# Enconder_Part2.net
KiCad netlist of a schematic drawn in Altium Designer
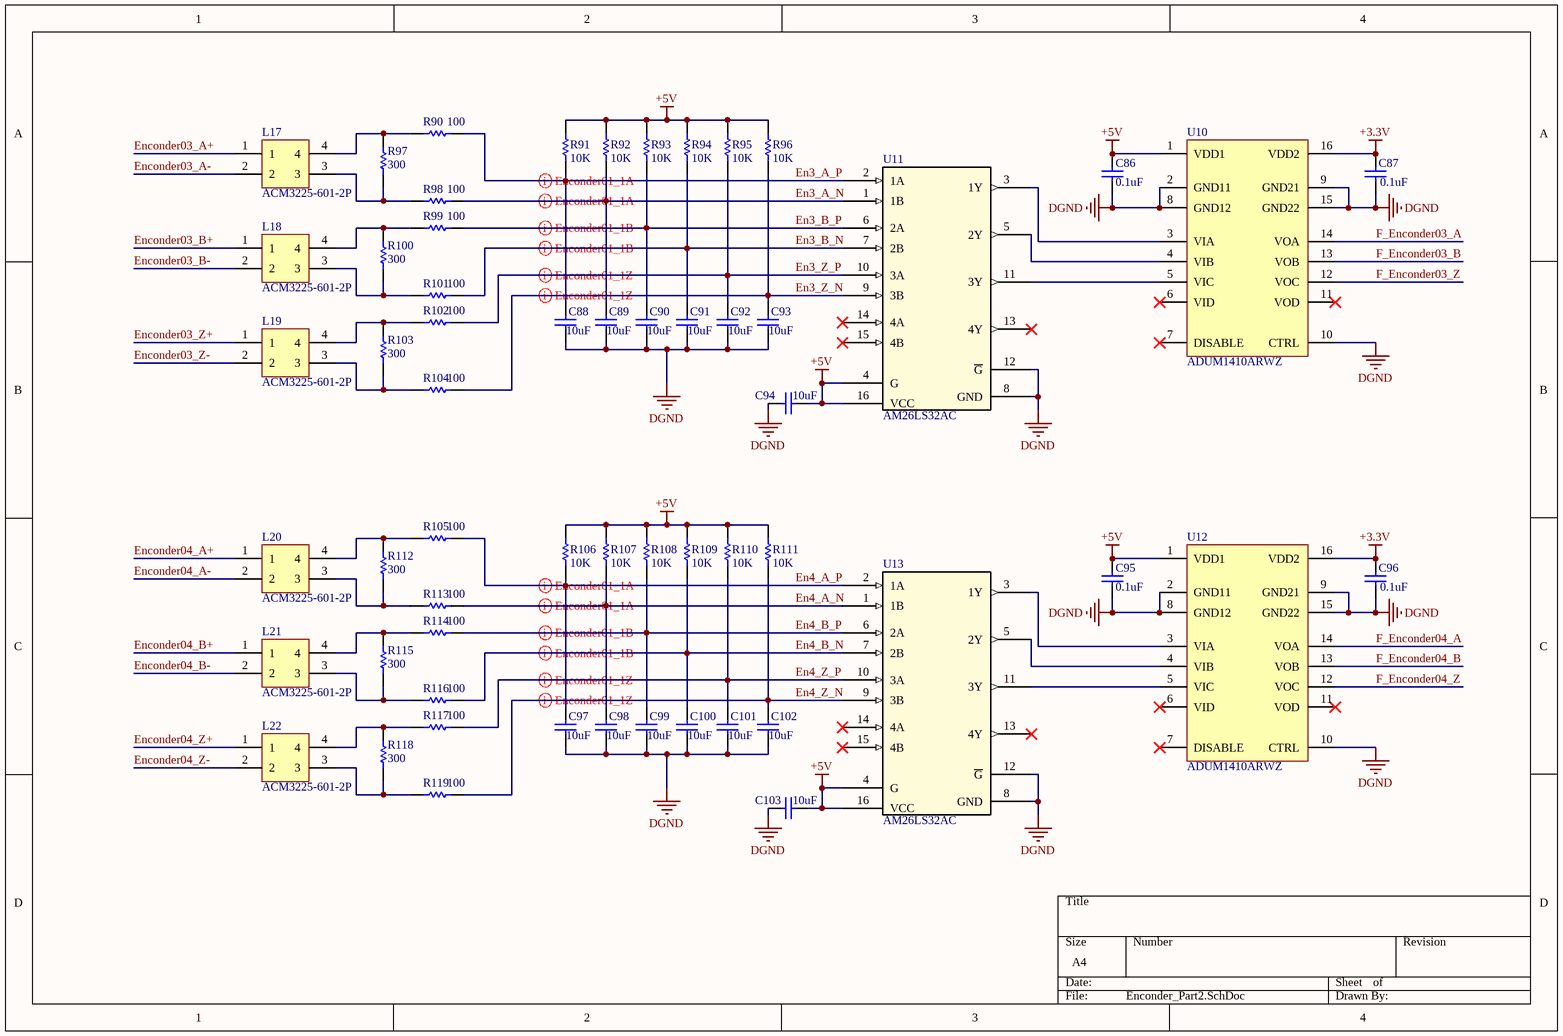
[diagram p0: Enconder_Part2.SchDoc]

(export (version "E")
  (design (tool "Eeschema 10.0.6"))
  (components
    (comp (ref "C86")
      (value "0.1uF")
      (footprint "1608[0603]")
      (description "Capacitor")
      (fields (field (name "Comment") "Cap") (field (name "PUBLISHER") "Altium Limited"))
      (libsource (lib "Miscellaneous Devices") (part "Cap"))
    )
    (comp (ref "C87")
      (value "0.1uF")
      (footprint "1608[0603]")
      (description "Capacitor")
      (fields (field (name "Comment") "Cap") (field (name "PUBLISHER") "Altium Limited"))
      (libsource (lib "Miscellaneous Devices") (part "Cap"))
    )
    (comp (ref "C88")
      (value "10uF")
      (footprint "1608[0603]")
      (description "Capacitor")
      (fields (field (name "Comment") "Cap") (field (name "PUBLISHER") "Altium Limited"))
      (libsource (lib "Miscellaneous Devices") (part "Cap"))
    )
    (comp (ref "C89")
      (value "10uF")
      (footprint "1608[0603]")
      (description "Capacitor")
      (fields (field (name "Comment") "Cap") (field (name "PUBLISHER") "Altium Limited"))
      (libsource (lib "Miscellaneous Devices") (part "Cap"))
    )
    (comp (ref "C90")
      (value "10uF")
      (footprint "1608[0603]")
      (description "Capacitor")
      (fields (field (name "Comment") "Cap") (field (name "PUBLISHER") "Altium Limited"))
      (libsource (lib "Miscellaneous Devices") (part "Cap"))
    )
    (comp (ref "C91")
      (value "10uF")
      (footprint "1608[0603]")
      (description "Capacitor")
      (fields (field (name "Comment") "Cap") (field (name "PUBLISHER") "Altium Limited"))
      (libsource (lib "Miscellaneous Devices") (part "Cap"))
    )
    (comp (ref "C92")
      (value "10uF")
      (footprint "1608[0603]")
      (description "Capacitor")
      (fields (field (name "Comment") "Cap") (field (name "PUBLISHER") "Altium Limited"))
      (libsource (lib "Miscellaneous Devices") (part "Cap"))
    )
    (comp (ref "C93")
      (value "10uF")
      (footprint "1608[0603]")
      (description "Capacitor")
      (fields (field (name "Comment") "Cap") (field (name "PUBLISHER") "Altium Limited"))
      (libsource (lib "Miscellaneous Devices") (part "Cap"))
    )
    (comp (ref "C94")
      (value "10uF")
      (footprint "1608[0603]")
      (description "Capacitor")
      (fields (field (name "Comment") "Cap") (field (name "PUBLISHER") "Altium Limited"))
      (libsource (lib "Miscellaneous Devices") (part "Cap"))
    )
    (comp (ref "C95")
      (value "0.1uF")
      (footprint "1608[0603]")
      (description "Capacitor")
      (fields (field (name "Comment") "Cap") (field (name "PUBLISHER") "Altium Limited"))
      (libsource (lib "Miscellaneous Devices") (part "Cap"))
    )
    (comp (ref "C96")
      (value "0.1uF")
      (footprint "1608[0603]")
      (description "Capacitor")
      (fields (field (name "Comment") "Cap") (field (name "PUBLISHER") "Altium Limited"))
      (libsource (lib "Miscellaneous Devices") (part "Cap"))
    )
    (comp (ref "C97")
      (value "10uF")
      (footprint "1608[0603]")
      (description "Capacitor")
      (fields (field (name "Comment") "Cap") (field (name "PUBLISHER") "Altium Limited"))
      (libsource (lib "Miscellaneous Devices") (part "Cap"))
    )
    (comp (ref "C98")
      (value "10uF")
      (footprint "1608[0603]")
      (description "Capacitor")
      (fields (field (name "Comment") "Cap") (field (name "PUBLISHER") "Altium Limited"))
      (libsource (lib "Miscellaneous Devices") (part "Cap"))
    )
    (comp (ref "C99")
      (value "10uF")
      (footprint "1608[0603]")
      (description "Capacitor")
      (fields (field (name "Comment") "Cap") (field (name "PUBLISHER") "Altium Limited"))
      (libsource (lib "Miscellaneous Devices") (part "Cap"))
    )
    (comp (ref "C100")
      (value "10uF")
      (footprint "1608[0603]")
      (description "Capacitor")
      (fields (field (name "Comment") "Cap") (field (name "PUBLISHER") "Altium Limited"))
      (libsource (lib "Miscellaneous Devices") (part "Cap"))
    )
    (comp (ref "C101")
      (value "10uF")
      (footprint "1608[0603]")
      (description "Capacitor")
      (fields (field (name "Comment") "Cap") (field (name "PUBLISHER") "Altium Limited"))
      (libsource (lib "Miscellaneous Devices") (part "Cap"))
    )
    (comp (ref "C102")
      (value "10uF")
      (footprint "1608[0603]")
      (description "Capacitor")
      (fields (field (name "Comment") "Cap") (field (name "PUBLISHER") "Altium Limited"))
      (libsource (lib "Miscellaneous Devices") (part "Cap"))
    )
    (comp (ref "C103")
      (value "10uF")
      (footprint "1608[0603]")
      (description "Capacitor")
      (fields (field (name "Comment") "Cap") (field (name "PUBLISHER") "Altium Limited"))
      (libsource (lib "Miscellaneous Devices") (part "Cap"))
    )
    (comp (ref "L17")
      (value "ACM3225-601-2P")
      (footprint "ACM3225-601-2P")
      (libsource (lib "DSP_FPGA_Lib") (part "ACM3225-601-2P"))
    )
    (comp (ref "L18")
      (value "ACM3225-601-2P")
      (footprint "ACM3225-601-2P")
      (libsource (lib "DSP_FPGA_Lib") (part "ACM3225-601-2P"))
    )
    (comp (ref "L19")
      (value "ACM3225-601-2P")
      (footprint "ACM3225-601-2P")
      (libsource (lib "DSP_FPGA_Lib") (part "ACM3225-601-2P"))
    )
    (comp (ref "L20")
      (value "ACM3225-601-2P")
      (footprint "ACM3225-601-2P")
      (libsource (lib "DSP_FPGA_Lib") (part "ACM3225-601-2P"))
    )
    (comp (ref "L21")
      (value "ACM3225-601-2P")
      (footprint "ACM3225-601-2P")
      (libsource (lib "DSP_FPGA_Lib") (part "ACM3225-601-2P"))
    )
    (comp (ref "L22")
      (value "ACM3225-601-2P")
      (footprint "ACM3225-601-2P")
      (libsource (lib "DSP_FPGA_Lib") (part "ACM3225-601-2P"))
    )
    (comp (ref "R90")
      (value "100")
      (footprint "1608[0603]")
      (description "Resistor")
      (fields (field (name "Comment") "Res1") (field (name "PUBLISHER") "Altium Limited"))
      (libsource (lib "Miscellaneous Devices") (part "Res1"))
    )
    (comp (ref "R91")
      (value "10K")
      (footprint "1608[0603]")
      (description "Resistor")
      (fields (field (name "Comment") "Res1") (field (name "PUBLISHER") "Altium Limited"))
      (libsource (lib "Miscellaneous Devices") (part "Res1"))
    )
    (comp (ref "R92")
      (value "10K")
      (footprint "1608[0603]")
      (description "Resistor")
      (fields (field (name "Comment") "Res1") (field (name "PUBLISHER") "Altium Limited"))
      (libsource (lib "Miscellaneous Devices") (part "Res1"))
    )
    (comp (ref "R93")
      (value "10K")
      (footprint "1608[0603]")
      (description "Resistor")
      (fields (field (name "Comment") "Res1") (field (name "PUBLISHER") "Altium Limited"))
      (libsource (lib "Miscellaneous Devices") (part "Res1"))
    )
    (comp (ref "R94")
      (value "10K")
      (footprint "1608[0603]")
      (description "Resistor")
      (fields (field (name "Comment") "Res1") (field (name "PUBLISHER") "Altium Limited"))
      (libsource (lib "Miscellaneous Devices") (part "Res1"))
    )
    (comp (ref "R95")
      (value "10K")
      (footprint "1608[0603]")
      (description "Resistor")
      (fields (field (name "Comment") "Res1") (field (name "PUBLISHER") "Altium Limited"))
      (libsource (lib "Miscellaneous Devices") (part "Res1"))
    )
    (comp (ref "R96")
      (value "10K")
      (footprint "1608[0603]")
      (description "Resistor")
      (fields (field (name "Comment") "Res1") (field (name "PUBLISHER") "Altium Limited"))
      (libsource (lib "Miscellaneous Devices") (part "Res1"))
    )
    (comp (ref "R97")
      (value "300")
      (footprint "1608[0603]")
      (description "Resistor")
      (fields (field (name "Comment") "Res1") (field (name "PUBLISHER") "Altium Limited"))
      (libsource (lib "Miscellaneous Devices") (part "Res1"))
    )
    (comp (ref "R98")
      (value "100")
      (footprint "1608[0603]")
      (description "Resistor")
      (fields (field (name "Comment") "Res1") (field (name "PUBLISHER") "Altium Limited"))
      (libsource (lib "Miscellaneous Devices") (part "Res1"))
    )
    (comp (ref "R99")
      (value "100")
      (footprint "1608[0603]")
      (description "Resistor")
      (fields (field (name "Comment") "Res1") (field (name "PUBLISHER") "Altium Limited"))
      (libsource (lib "Miscellaneous Devices") (part "Res1"))
    )
    (comp (ref "R100")
      (value "300")
      (footprint "1608[0603]")
      (description "Resistor")
      (fields (field (name "Comment") "Res1") (field (name "PUBLISHER") "Altium Limited"))
      (libsource (lib "Miscellaneous Devices") (part "Res1"))
    )
    (comp (ref "R101")
      (value "100")
      (footprint "1608[0603]")
      (description "Resistor")
      (fields (field (name "Comment") "Res1") (field (name "PUBLISHER") "Altium Limited"))
      (libsource (lib "Miscellaneous Devices") (part "Res1"))
    )
    (comp (ref "R102")
      (value "100")
      (footprint "1608[0603]")
      (description "Resistor")
      (fields (field (name "Comment") "Res1") (field (name "PUBLISHER") "Altium Limited"))
      (libsource (lib "Miscellaneous Devices") (part "Res1"))
    )
    (comp (ref "R103")
      (value "300")
      (footprint "1608[0603]")
      (description "Resistor")
      (fields (field (name "Comment") "Res1") (field (name "PUBLISHER") "Altium Limited"))
      (libsource (lib "Miscellaneous Devices") (part "Res1"))
    )
    (comp (ref "R104")
      (value "100")
      (footprint "1608[0603]")
      (description "Resistor")
      (fields (field (name "Comment") "Res1") (field (name "PUBLISHER") "Altium Limited"))
      (libsource (lib "Miscellaneous Devices") (part "Res1"))
    )
    (comp (ref "R105")
      (value "100")
      (footprint "1608[0603]")
      (description "Resistor")
      (fields (field (name "Comment") "Res1") (field (name "PUBLISHER") "Altium Limited"))
      (libsource (lib "Miscellaneous Devices") (part "Res1"))
    )
    (comp (ref "R106")
      (value "10K")
      (footprint "1608[0603]")
      (description "Resistor")
      (fields (field (name "Comment") "Res1") (field (name "PUBLISHER") "Altium Limited"))
      (libsource (lib "Miscellaneous Devices") (part "Res1"))
    )
    (comp (ref "R107")
      (value "10K")
      (footprint "1608[0603]")
      (description "Resistor")
      (fields (field (name "Comment") "Res1") (field (name "PUBLISHER") "Altium Limited"))
      (libsource (lib "Miscellaneous Devices") (part "Res1"))
    )
    (comp (ref "R108")
      (value "10K")
      (footprint "1608[0603]")
      (description "Resistor")
      (fields (field (name "Comment") "Res1") (field (name "PUBLISHER") "Altium Limited"))
      (libsource (lib "Miscellaneous Devices") (part "Res1"))
    )
    (comp (ref "R109")
      (value "10K")
      (footprint "1608[0603]")
      (description "Resistor")
      (fields (field (name "Comment") "Res1") (field (name "PUBLISHER") "Altium Limited"))
      (libsource (lib "Miscellaneous Devices") (part "Res1"))
    )
    (comp (ref "R110")
      (value "10K")
      (footprint "1608[0603]")
      (description "Resistor")
      (fields (field (name "Comment") "Res1") (field (name "PUBLISHER") "Altium Limited"))
      (libsource (lib "Miscellaneous Devices") (part "Res1"))
    )
    (comp (ref "R111")
      (value "10K")
      (footprint "1608[0603]")
      (description "Resistor")
      (fields (field (name "Comment") "Res1") (field (name "PUBLISHER") "Altium Limited"))
      (libsource (lib "Miscellaneous Devices") (part "Res1"))
    )
    (comp (ref "R112")
      (value "300")
      (footprint "1608[0603]")
      (description "Resistor")
      (fields (field (name "Comment") "Res1") (field (name "PUBLISHER") "Altium Limited"))
      (libsource (lib "Miscellaneous Devices") (part "Res1"))
    )
    (comp (ref "R113")
      (value "100")
      (footprint "1608[0603]")
      (description "Resistor")
      (fields (field (name "Comment") "Res1") (field (name "PUBLISHER") "Altium Limited"))
      (libsource (lib "Miscellaneous Devices") (part "Res1"))
    )
    (comp (ref "R114")
      (value "100")
      (footprint "1608[0603]")
      (description "Resistor")
      (fields (field (name "Comment") "Res1") (field (name "PUBLISHER") "Altium Limited"))
      (libsource (lib "Miscellaneous Devices") (part "Res1"))
    )
    (comp (ref "R115")
      (value "300")
      (footprint "1608[0603]")
      (description "Resistor")
      (fields (field (name "Comment") "Res1") (field (name "PUBLISHER") "Altium Limited"))
      (libsource (lib "Miscellaneous Devices") (part "Res1"))
    )
    (comp (ref "R116")
      (value "100")
      (footprint "1608[0603]")
      (description "Resistor")
      (fields (field (name "Comment") "Res1") (field (name "PUBLISHER") "Altium Limited"))
      (libsource (lib "Miscellaneous Devices") (part "Res1"))
    )
    (comp (ref "R117")
      (value "100")
      (footprint "1608[0603]")
      (description "Resistor")
      (fields (field (name "Comment") "Res1") (field (name "PUBLISHER") "Altium Limited"))
      (libsource (lib "Miscellaneous Devices") (part "Res1"))
    )
    (comp (ref "R118")
      (value "300")
      (footprint "1608[0603]")
      (description "Resistor")
      (fields (field (name "Comment") "Res1") (field (name "PUBLISHER") "Altium Limited"))
      (libsource (lib "Miscellaneous Devices") (part "Res1"))
    )
    (comp (ref "R119")
      (value "100")
      (footprint "1608[0603]")
      (description "Resistor")
      (fields (field (name "Comment") "Res1") (field (name "PUBLISHER") "Altium Limited"))
      (libsource (lib "Miscellaneous Devices") (part "Res1"))
    )
    (comp (ref "U10")
      (value "ADUM1410ARWZ")
      (footprint "ADUM1410ARWZ_SOIC")
      (libsource (lib "DSP_FPGA_Lib") (part "ADUM1410ARWZ"))
    )
    (comp (ref "U11")
      (value "AM26LS32AC")
      (footprint "AM26LS32AC_SOP")
      (libsource (lib "DSP_FPGA_Lib") (part "AM26LS32AC"))
    )
    (comp (ref "U12")
      (value "ADUM1410ARWZ")
      (footprint "ADUM1410ARWZ_SOIC")
      (libsource (lib "DSP_FPGA_Lib") (part "ADUM1410ARWZ"))
    )
    (comp (ref "U13")
      (value "AM26LS32AC")
      (footprint "AM26LS32AC_SOP")
      (libsource (lib "DSP_FPGA_Lib") (part "AM26LS32AC"))
    )
  )
  (nets
    (net (code "1") (name "+3.3V") (class "Default")
      (node (ref "C87") (pin "2") (pinfunction "2_2") (pintype "passive"))
      (node (ref "C96") (pin "2") (pinfunction "2_2") (pintype "passive"))
      (node (ref "U10") (pin "16") (pinfunction "VDD2_16") (pintype "passive"))
      (node (ref "U12") (pin "16") (pinfunction "VDD2_16") (pintype "passive"))
    )
    (net (code "2") (name "+5V") (class "Default")
      (node (ref "C103") (pin "1") (pinfunction "1_1") (pintype "passive"))
      (node (ref "C86") (pin "2") (pinfunction "2_2") (pintype "passive"))
      (node (ref "C94") (pin "1") (pinfunction "1_1") (pintype "passive"))
      (node (ref "C95") (pin "2") (pinfunction "2_2") (pintype "passive"))
      (node (ref "R106") (pin "2") (pinfunction "2_2") (pintype "passive"))
      (node (ref "R107") (pin "2") (pinfunction "2_2") (pintype "passive"))
      (node (ref "R108") (pin "2") (pinfunction "2_2") (pintype "passive"))
      (node (ref "R109") (pin "2") (pinfunction "2_2") (pintype "passive"))
      (node (ref "R110") (pin "2") (pinfunction "2_2") (pintype "passive"))
      (node (ref "R111") (pin "2") (pinfunction "2_2") (pintype "passive"))
      (node (ref "R91") (pin "2") (pinfunction "2_2") (pintype "passive"))
      (node (ref "R92") (pin "2") (pinfunction "2_2") (pintype "passive"))
      (node (ref "R93") (pin "2") (pinfunction "2_2") (pintype "passive"))
      (node (ref "R94") (pin "2") (pinfunction "2_2") (pintype "passive"))
      (node (ref "R95") (pin "2") (pinfunction "2_2") (pintype "passive"))
      (node (ref "R96") (pin "2") (pinfunction "2_2") (pintype "passive"))
      (node (ref "U10") (pin "1") (pinfunction "VDD1_1") (pintype "passive"))
      (node (ref "U11") (pin "16") (pinfunction "VCC_16") (pintype "power_in"))
      (node (ref "U11") (pin "4") (pinfunction "G_4") (pintype "passive"))
      (node (ref "U12") (pin "1") (pinfunction "VDD1_1") (pintype "passive"))
      (node (ref "U13") (pin "16") (pinfunction "VCC_16") (pintype "power_in"))
      (node (ref "U13") (pin "4") (pinfunction "G_4") (pintype "passive"))
    )
    (net (code "3") (name "/En3_A_N") (class "Default")
      (node (ref "C89") (pin "2") (pinfunction "2_2") (pintype "passive"))
      (node (ref "R92") (pin "1") (pinfunction "1_1") (pintype "passive"))
      (node (ref "R98") (pin "2") (pinfunction "2_2") (pintype "passive"))
      (node (ref "U11") (pin "1") (pinfunction "1B_1") (pintype "input"))
    )
    (net (code "4") (name "/En3_A_P") (class "Default")
      (node (ref "C88") (pin "2") (pinfunction "2_2") (pintype "passive"))
      (node (ref "R90") (pin "2") (pinfunction "2_2") (pintype "passive"))
      (node (ref "R91") (pin "1") (pinfunction "1_1") (pintype "passive"))
      (node (ref "U11") (pin "2") (pinfunction "1A_2") (pintype "input"))
    )
    (net (code "5") (name "/En3_B_N") (class "Default")
      (node (ref "C91") (pin "2") (pinfunction "2_2") (pintype "passive"))
      (node (ref "R101") (pin "2") (pinfunction "2_2") (pintype "passive"))
      (node (ref "R94") (pin "1") (pinfunction "1_1") (pintype "passive"))
      (node (ref "U11") (pin "7") (pinfunction "2B_7") (pintype "input"))
    )
    (net (code "6") (name "/En3_B_P") (class "Default")
      (node (ref "C90") (pin "2") (pinfunction "2_2") (pintype "passive"))
      (node (ref "R93") (pin "1") (pinfunction "1_1") (pintype "passive"))
      (node (ref "R99") (pin "2") (pinfunction "2_2") (pintype "passive"))
      (node (ref "U11") (pin "6") (pinfunction "2A_6") (pintype "input"))
    )
    (net (code "7") (name "/En3_Z_N") (class "Default")
      (node (ref "C93") (pin "2") (pinfunction "2_2") (pintype "passive"))
      (node (ref "R104") (pin "2") (pinfunction "2_2") (pintype "passive"))
      (node (ref "R96") (pin "1") (pinfunction "1_1") (pintype "passive"))
      (node (ref "U11") (pin "9") (pinfunction "3B_9") (pintype "input"))
    )
    (net (code "8") (name "/En3_Z_P") (class "Default")
      (node (ref "C92") (pin "2") (pinfunction "2_2") (pintype "passive"))
      (node (ref "R102") (pin "2") (pinfunction "2_2") (pintype "passive"))
      (node (ref "R95") (pin "1") (pinfunction "1_1") (pintype "passive"))
      (node (ref "U11") (pin "10") (pinfunction "3A_10") (pintype "input"))
    )
    (net (code "9") (name "/En4_A_N") (class "Default")
      (node (ref "C98") (pin "2") (pinfunction "2_2") (pintype "passive"))
      (node (ref "R107") (pin "1") (pinfunction "1_1") (pintype "passive"))
      (node (ref "R113") (pin "2") (pinfunction "2_2") (pintype "passive"))
      (node (ref "U13") (pin "1") (pinfunction "1B_1") (pintype "input"))
    )
    (net (code "10") (name "/En4_A_P") (class "Default")
      (node (ref "C97") (pin "2") (pinfunction "2_2") (pintype "passive"))
      (node (ref "R105") (pin "2") (pinfunction "2_2") (pintype "passive"))
      (node (ref "R106") (pin "1") (pinfunction "1_1") (pintype "passive"))
      (node (ref "U13") (pin "2") (pinfunction "1A_2") (pintype "input"))
    )
    (net (code "11") (name "/En4_B_N") (class "Default")
      (node (ref "C100") (pin "2") (pinfunction "2_2") (pintype "passive"))
      (node (ref "R109") (pin "1") (pinfunction "1_1") (pintype "passive"))
      (node (ref "R116") (pin "2") (pinfunction "2_2") (pintype "passive"))
      (node (ref "U13") (pin "7") (pinfunction "2B_7") (pintype "input"))
    )
    (net (code "12") (name "/En4_B_P") (class "Default")
      (node (ref "C99") (pin "2") (pinfunction "2_2") (pintype "passive"))
      (node (ref "R108") (pin "1") (pinfunction "1_1") (pintype "passive"))
      (node (ref "R114") (pin "2") (pinfunction "2_2") (pintype "passive"))
      (node (ref "U13") (pin "6") (pinfunction "2A_6") (pintype "input"))
    )
    (net (code "13") (name "/En4_Z_N") (class "Default")
      (node (ref "C102") (pin "2") (pinfunction "2_2") (pintype "passive"))
      (node (ref "R111") (pin "1") (pinfunction "1_1") (pintype "passive"))
      (node (ref "R119") (pin "2") (pinfunction "2_2") (pintype "passive"))
      (node (ref "U13") (pin "9") (pinfunction "3B_9") (pintype "input"))
    )
    (net (code "14") (name "/En4_Z_P") (class "Default")
      (node (ref "C101") (pin "2") (pinfunction "2_2") (pintype "passive"))
      (node (ref "R110") (pin "1") (pinfunction "1_1") (pintype "passive"))
      (node (ref "R117") (pin "2") (pinfunction "2_2") (pintype "passive"))
      (node (ref "U13") (pin "10") (pinfunction "3A_10") (pintype "input"))
    )
    (net (code "15") (name "/Enconder03_A+") (class "Default")
      (node (ref "L17") (pin "1") (pinfunction "1_1") (pintype "passive"))
    )
    (net (code "16") (name "/Enconder03_A-") (class "Default")
      (node (ref "L17") (pin "2") (pinfunction "2_2") (pintype "passive"))
    )
    (net (code "17") (name "/Enconder03_B+") (class "Default")
      (node (ref "L18") (pin "1") (pinfunction "1_1") (pintype "passive"))
    )
    (net (code "18") (name "/Enconder03_B-") (class "Default")
      (node (ref "L18") (pin "2") (pinfunction "2_2") (pintype "passive"))
    )
    (net (code "19") (name "/Enconder03_Z+") (class "Default")
      (node (ref "L19") (pin "1") (pinfunction "1_1") (pintype "passive"))
    )
    (net (code "20") (name "/Enconder03_Z-") (class "Default")
      (node (ref "L19") (pin "2") (pinfunction "2_2") (pintype "passive"))
    )
    (net (code "21") (name "/Enconder04_A+") (class "Default")
      (node (ref "L20") (pin "1") (pinfunction "1_1") (pintype "passive"))
    )
    (net (code "22") (name "/Enconder04_A-") (class "Default")
      (node (ref "L20") (pin "2") (pinfunction "2_2") (pintype "passive"))
    )
    (net (code "23") (name "/Enconder04_B+") (class "Default")
      (node (ref "L21") (pin "1") (pinfunction "1_1") (pintype "passive"))
    )
    (net (code "24") (name "/Enconder04_B-") (class "Default")
      (node (ref "L21") (pin "2") (pinfunction "2_2") (pintype "passive"))
    )
    (net (code "25") (name "/Enconder04_Z+") (class "Default")
      (node (ref "L22") (pin "1") (pinfunction "1_1") (pintype "passive"))
    )
    (net (code "26") (name "/Enconder04_Z-") (class "Default")
      (node (ref "L22") (pin "2") (pinfunction "2_2") (pintype "passive"))
    )
    (net (code "27") (name "/F_Enconder03_A") (class "Default")
      (node (ref "U10") (pin "14") (pinfunction "VOA_14") (pintype "passive"))
    )
    (net (code "28") (name "/F_Enconder03_B") (class "Default")
      (node (ref "U10") (pin "13") (pinfunction "VOB_13") (pintype "passive"))
    )
    (net (code "29") (name "/F_Enconder03_Z") (class "Default")
      (node (ref "U10") (pin "12") (pinfunction "VOC_12") (pintype "passive"))
    )
    (net (code "30") (name "/F_Enconder04_A") (class "Default")
      (node (ref "U12") (pin "14") (pinfunction "VOA_14") (pintype "passive"))
    )
    (net (code "31") (name "/F_Enconder04_B") (class "Default")
      (node (ref "U12") (pin "13") (pinfunction "VOB_13") (pintype "passive"))
    )
    (net (code "32") (name "/F_Enconder04_Z") (class "Default")
      (node (ref "U12") (pin "12") (pinfunction "VOC_12") (pintype "passive"))
    )
    (net (code "33") (name "DGND") (class "Default")
      (node (ref "C100") (pin "1") (pinfunction "1_1") (pintype "passive"))
      (node (ref "C101") (pin "1") (pinfunction "1_1") (pintype "passive"))
      (node (ref "C102") (pin "1") (pinfunction "1_1") (pintype "passive"))
      (node (ref "C103") (pin "2") (pinfunction "2_2") (pintype "passive"))
      (node (ref "C86") (pin "1") (pinfunction "1_1") (pintype "passive"))
      (node (ref "C87") (pin "1") (pinfunction "1_1") (pintype "passive"))
      (node (ref "C88") (pin "1") (pinfunction "1_1") (pintype "passive"))
      (node (ref "C89") (pin "1") (pinfunction "1_1") (pintype "passive"))
      (node (ref "C90") (pin "1") (pinfunction "1_1") (pintype "passive"))
      (node (ref "C91") (pin "1") (pinfunction "1_1") (pintype "passive"))
      (node (ref "C92") (pin "1") (pinfunction "1_1") (pintype "passive"))
      (node (ref "C93") (pin "1") (pinfunction "1_1") (pintype "passive"))
      (node (ref "C94") (pin "2") (pinfunction "2_2") (pintype "passive"))
      (node (ref "C95") (pin "1") (pinfunction "1_1") (pintype "passive"))
      (node (ref "C96") (pin "1") (pinfunction "1_1") (pintype "passive"))
      (node (ref "C97") (pin "1") (pinfunction "1_1") (pintype "passive"))
      (node (ref "C98") (pin "1") (pinfunction "1_1") (pintype "passive"))
      (node (ref "C99") (pin "1") (pinfunction "1_1") (pintype "passive"))
      (node (ref "U10") (pin "10") (pinfunction "CTRL_10") (pintype "passive"))
      (node (ref "U10") (pin "15") (pinfunction "GND22_15") (pintype "passive"))
      (node (ref "U10") (pin "2") (pinfunction "GND11_2") (pintype "passive"))
      (node (ref "U10") (pin "8") (pinfunction "GND12_8") (pintype "passive"))
      (node (ref "U10") (pin "9") (pinfunction "GND21_9") (pintype "passive"))
      (node (ref "U11") (pin "12") (pinfunction "~{G}_12") (pintype "passive"))
      (node (ref "U11") (pin "8") (pinfunction "GND_8") (pintype "power_in"))
      (node (ref "U12") (pin "10") (pinfunction "CTRL_10") (pintype "passive"))
      (node (ref "U12") (pin "15") (pinfunction "GND22_15") (pintype "passive"))
      (node (ref "U12") (pin "2") (pinfunction "GND11_2") (pintype "passive"))
      (node (ref "U12") (pin "8") (pinfunction "GND12_8") (pintype "passive"))
      (node (ref "U12") (pin "9") (pinfunction "GND21_9") (pintype "passive"))
      (node (ref "U13") (pin "12") (pinfunction "~{G}_12") (pintype "passive"))
      (node (ref "U13") (pin "8") (pinfunction "GND_8") (pintype "power_in"))
    )
    (net (code "34") (name "Net-(L17-Pad3)") (class "Default")
      (node (ref "L17") (pin "3") (pinfunction "3_3") (pintype "passive"))
      (node (ref "R97") (pin "1") (pinfunction "1_1") (pintype "passive"))
      (node (ref "R98") (pin "1") (pinfunction "1_1") (pintype "passive"))
    )
    (net (code "35") (name "Net-(L17-Pad4)") (class "Default")
      (node (ref "L17") (pin "4") (pinfunction "4_4") (pintype "passive"))
      (node (ref "R90") (pin "1") (pinfunction "1_1") (pintype "passive"))
      (node (ref "R97") (pin "2") (pinfunction "2_2") (pintype "passive"))
    )
    (net (code "36") (name "Net-(L18-Pad3)") (class "Default")
      (node (ref "L18") (pin "3") (pinfunction "3_3") (pintype "passive"))
      (node (ref "R100") (pin "1") (pinfunction "1_1") (pintype "passive"))
      (node (ref "R101") (pin "1") (pinfunction "1_1") (pintype "passive"))
    )
    (net (code "37") (name "Net-(L18-Pad4)") (class "Default")
      (node (ref "L18") (pin "4") (pinfunction "4_4") (pintype "passive"))
      (node (ref "R100") (pin "2") (pinfunction "2_2") (pintype "passive"))
      (node (ref "R99") (pin "1") (pinfunction "1_1") (pintype "passive"))
    )
    (net (code "38") (name "Net-(L19-Pad3)") (class "Default")
      (node (ref "L19") (pin "3") (pinfunction "3_3") (pintype "passive"))
      (node (ref "R103") (pin "1") (pinfunction "1_1") (pintype "passive"))
      (node (ref "R104") (pin "1") (pinfunction "1_1") (pintype "passive"))
    )
    (net (code "39") (name "Net-(L19-Pad4)") (class "Default")
      (node (ref "L19") (pin "4") (pinfunction "4_4") (pintype "passive"))
      (node (ref "R102") (pin "1") (pinfunction "1_1") (pintype "passive"))
      (node (ref "R103") (pin "2") (pinfunction "2_2") (pintype "passive"))
    )
    (net (code "40") (name "Net-(L20-Pad3)") (class "Default")
      (node (ref "L20") (pin "3") (pinfunction "3_3") (pintype "passive"))
      (node (ref "R112") (pin "1") (pinfunction "1_1") (pintype "passive"))
      (node (ref "R113") (pin "1") (pinfunction "1_1") (pintype "passive"))
    )
    (net (code "41") (name "Net-(L20-Pad4)") (class "Default")
      (node (ref "L20") (pin "4") (pinfunction "4_4") (pintype "passive"))
      (node (ref "R105") (pin "1") (pinfunction "1_1") (pintype "passive"))
      (node (ref "R112") (pin "2") (pinfunction "2_2") (pintype "passive"))
    )
    (net (code "42") (name "Net-(L21-Pad3)") (class "Default")
      (node (ref "L21") (pin "3") (pinfunction "3_3") (pintype "passive"))
      (node (ref "R115") (pin "1") (pinfunction "1_1") (pintype "passive"))
      (node (ref "R116") (pin "1") (pinfunction "1_1") (pintype "passive"))
    )
    (net (code "43") (name "Net-(L21-Pad4)") (class "Default")
      (node (ref "L21") (pin "4") (pinfunction "4_4") (pintype "passive"))
      (node (ref "R114") (pin "1") (pinfunction "1_1") (pintype "passive"))
      (node (ref "R115") (pin "2") (pinfunction "2_2") (pintype "passive"))
    )
    (net (code "44") (name "Net-(L22-Pad3)") (class "Default")
      (node (ref "L22") (pin "3") (pinfunction "3_3") (pintype "passive"))
      (node (ref "R118") (pin "1") (pinfunction "1_1") (pintype "passive"))
      (node (ref "R119") (pin "1") (pinfunction "1_1") (pintype "passive"))
    )
    (net (code "45") (name "Net-(L22-Pad4)") (class "Default")
      (node (ref "L22") (pin "4") (pinfunction "4_4") (pintype "passive"))
      (node (ref "R117") (pin "1") (pinfunction "1_1") (pintype "passive"))
      (node (ref "R118") (pin "2") (pinfunction "2_2") (pintype "passive"))
    )
    (net (code "46") (name "Net-(U10-VIA)") (class "Default")
      (node (ref "U10") (pin "3") (pinfunction "VIA_3") (pintype "passive"))
      (node (ref "U11") (pin "3") (pinfunction "1Y_3") (pintype "output"))
    )
    (net (code "47") (name "Net-(U10-VIB)") (class "Default")
      (node (ref "U10") (pin "4") (pinfunction "VIB_4") (pintype "passive"))
      (node (ref "U11") (pin "5") (pinfunction "2Y_5") (pintype "output"))
    )
    (net (code "48") (name "Net-(U10-VIC)") (class "Default")
      (node (ref "U10") (pin "5") (pinfunction "VIC_5") (pintype "passive"))
      (node (ref "U11") (pin "11") (pinfunction "3Y_11") (pintype "output"))
    )
    (net (code "49") (name "Net-(U12-VIA)") (class "Default")
      (node (ref "U12") (pin "3") (pinfunction "VIA_3") (pintype "passive"))
      (node (ref "U13") (pin "3") (pinfunction "1Y_3") (pintype "output"))
    )
    (net (code "50") (name "Net-(U12-VIB)") (class "Default")
      (node (ref "U12") (pin "4") (pinfunction "VIB_4") (pintype "passive"))
      (node (ref "U13") (pin "5") (pinfunction "2Y_5") (pintype "output"))
    )
    (net (code "51") (name "Net-(U12-VIC)") (class "Default")
      (node (ref "U12") (pin "5") (pinfunction "VIC_5") (pintype "passive"))
      (node (ref "U13") (pin "11") (pinfunction "3Y_11") (pintype "output"))
    )
    (net (code "52") (name "unconnected-(U10-DISABLE-Pad7)") (class "Default")
      (node (ref "U10") (pin "7") (pinfunction "DISABLE_7") (pintype "passive+no_connect"))
    )
    (net (code "53") (name "unconnected-(U10-VID-Pad6)") (class "Default")
      (node (ref "U10") (pin "6") (pinfunction "VID_6") (pintype "passive+no_connect"))
    )
    (net (code "54") (name "unconnected-(U10-VOD-Pad11)") (class "Default")
      (node (ref "U10") (pin "11") (pinfunction "VOD_11") (pintype "passive+no_connect"))
    )
    (net (code "55") (name "unconnected-(U11-4A-Pad14)") (class "Default")
      (node (ref "U11") (pin "14") (pinfunction "4A_14") (pintype "input+no_connect"))
    )
    (net (code "56") (name "unconnected-(U11-4B-Pad15)") (class "Default")
      (node (ref "U11") (pin "15") (pinfunction "4B_15") (pintype "input+no_connect"))
    )
    (net (code "57") (name "unconnected-(U11-4Y-Pad13)") (class "Default")
      (node (ref "U11") (pin "13") (pinfunction "4Y_13") (pintype "output+no_connect"))
    )
    (net (code "58") (name "unconnected-(U12-DISABLE-Pad7)") (class "Default")
      (node (ref "U12") (pin "7") (pinfunction "DISABLE_7") (pintype "passive+no_connect"))
    )
    (net (code "59") (name "unconnected-(U12-VID-Pad6)") (class "Default")
      (node (ref "U12") (pin "6") (pinfunction "VID_6") (pintype "passive+no_connect"))
    )
    (net (code "60") (name "unconnected-(U12-VOD-Pad11)") (class "Default")
      (node (ref "U12") (pin "11") (pinfunction "VOD_11") (pintype "passive+no_connect"))
    )
    (net (code "61") (name "unconnected-(U13-4A-Pad14)") (class "Default")
      (node (ref "U13") (pin "14") (pinfunction "4A_14") (pintype "input+no_connect"))
    )
    (net (code "62") (name "unconnected-(U13-4B-Pad15)") (class "Default")
      (node (ref "U13") (pin "15") (pinfunction "4B_15") (pintype "input+no_connect"))
    )
    (net (code "63") (name "unconnected-(U13-4Y-Pad13)") (class "Default")
      (node (ref "U13") (pin "13") (pinfunction "4Y_13") (pintype "output+no_connect"))
    )
  )
)
